# clock.net
KiCad netlist of a schematic drawn in EAGLE
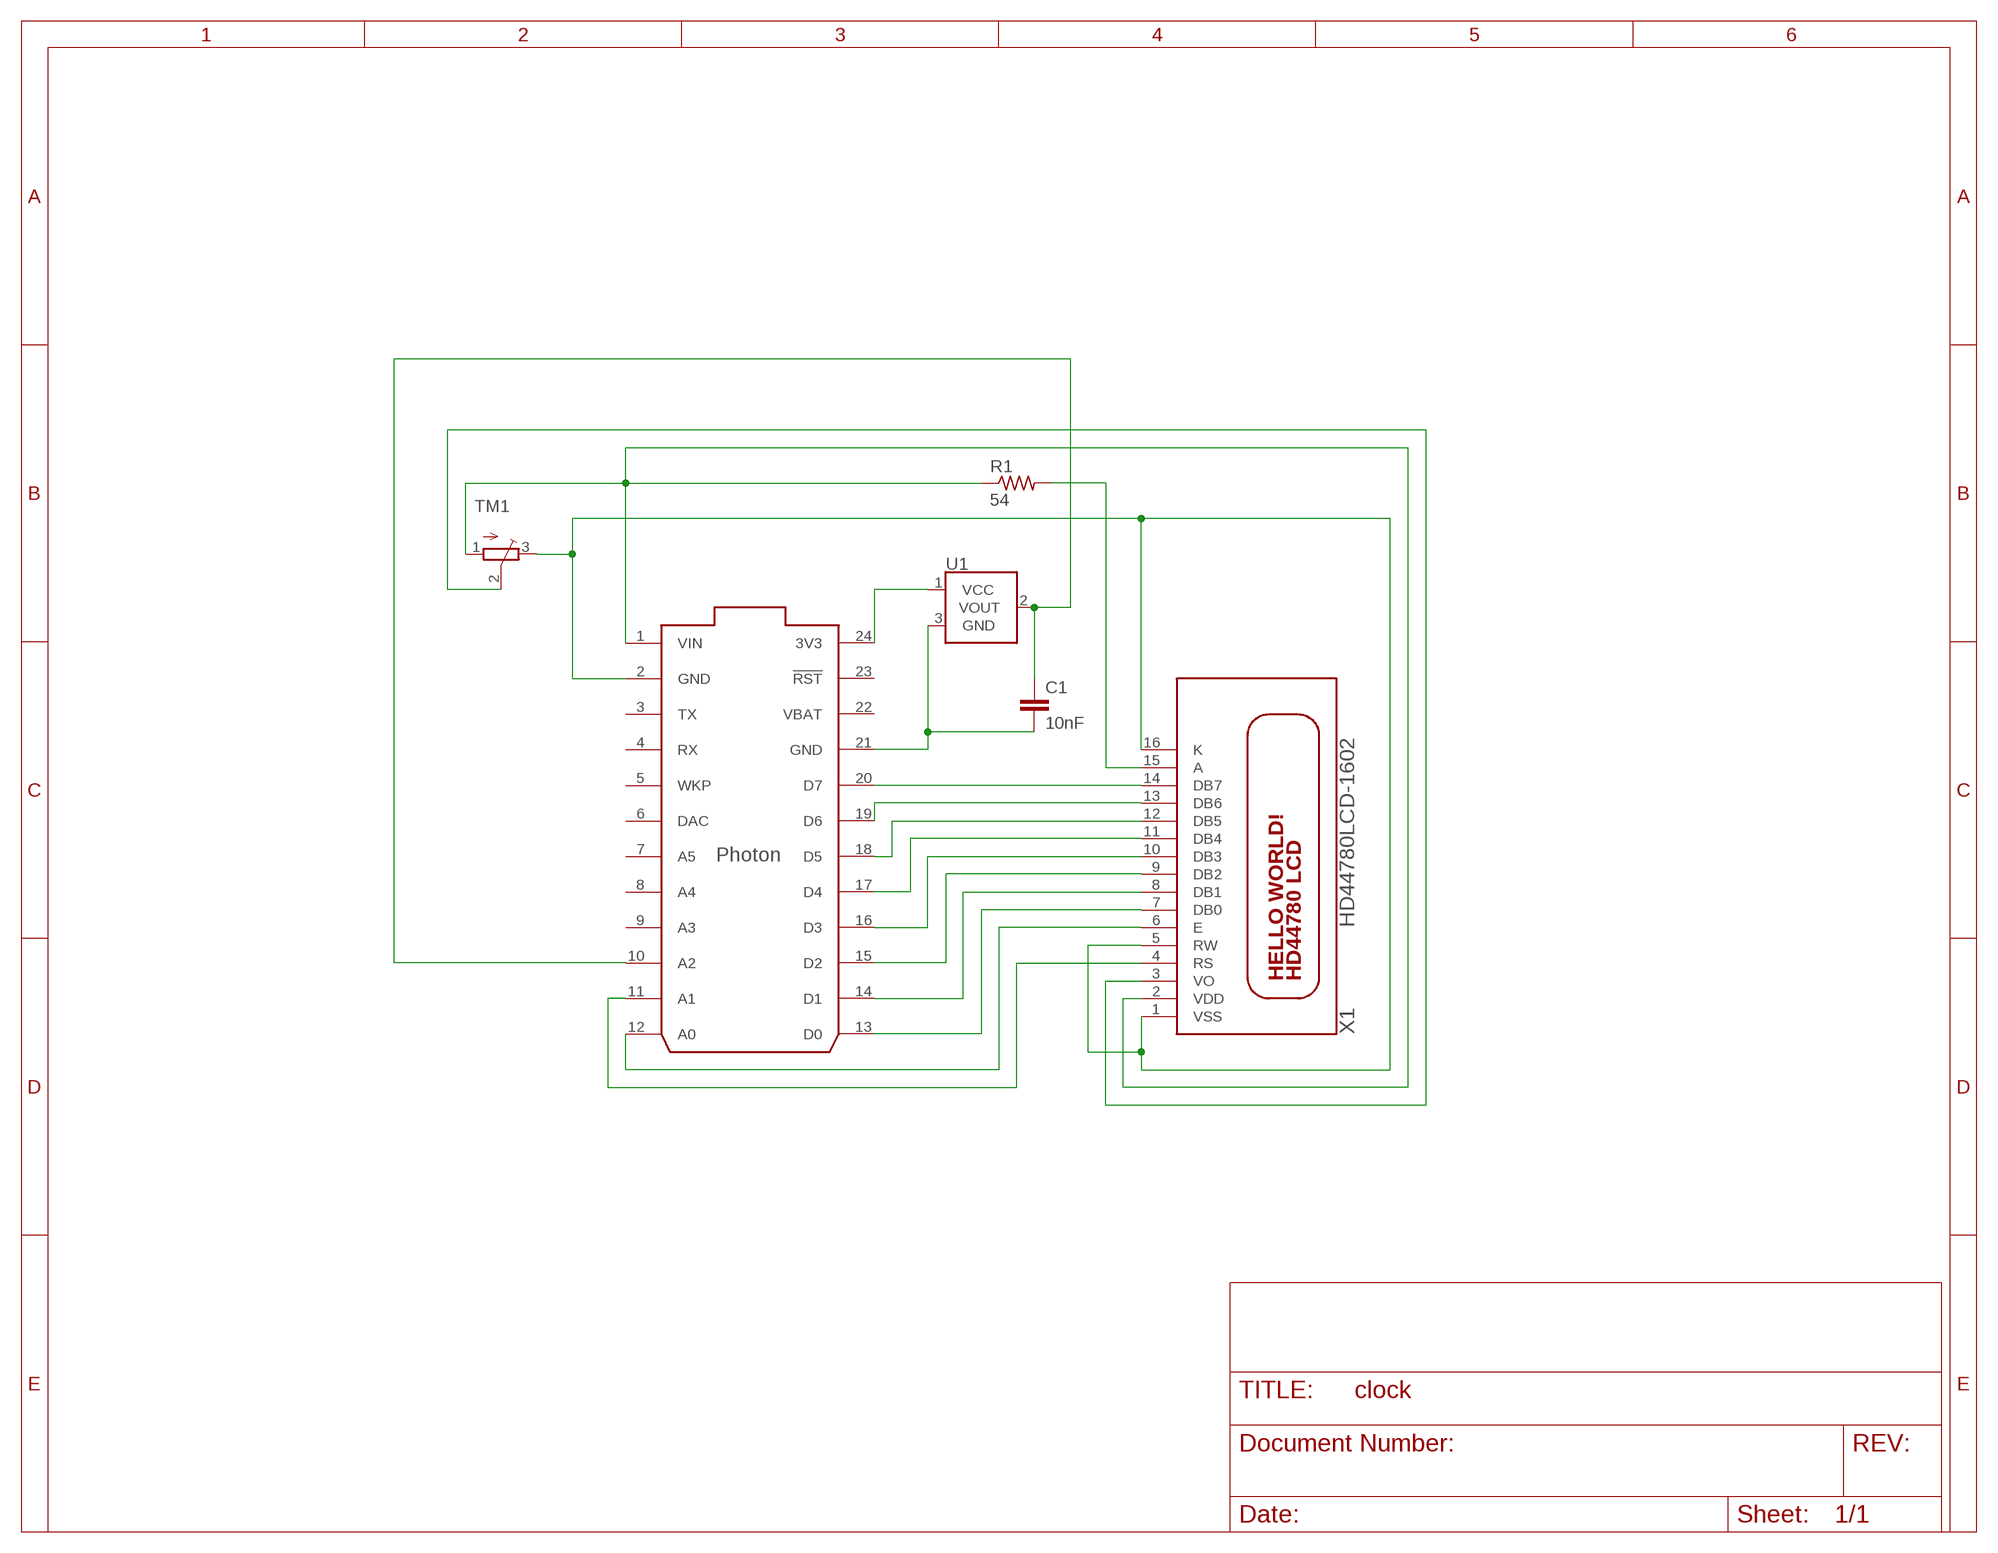
[diagram p0: schematic, sheet 1]

(export (version "E")
  (design (tool "Eeschema 10.0.6"))
  (components
    (comp (ref "C1")
      (value "10nF")
      (footprint "eagle-import:CAP-PTH-10MM")
      (libsource (lib "eagle-import") (part "10NF-PTH-10MM-10000V-1-%"))
    )
    (comp (ref "R1")
      (value "54")
      (footprint "eagle-import:0309_12")
      (libsource (lib "eagle-import") (part "R-US_0309/12"))
    )
    (comp (ref "TM1")
      (value "TRIMPOT3386")
      (footprint "eagle-import:TRIM-3386")
      (libsource (lib "eagle-import") (part "TRIMPOT3386"))
    )
    (comp (ref "U$1")
      (value "PHOTON_WITH_HEADERS")
      (footprint "eagle-import:PHOTON")
      (libsource (lib "eagle-import") (part "PHOTON_WITH_HEADERS"))
    )
    (comp (ref "U1")
      (value "TMP36GT9")
      (footprint "eagle-import:TO-92")
      (libsource (lib "eagle-import") (part "TMP36GT9"))
    )
    (comp (ref "X1")
      (value "HD44780LCD-1602")
      (footprint "eagle-import:LCD1602")
      (libsource (lib "eagle-import") (part "HD44780LCD-1602"))
    )
  )
  (nets
    (net (code "1") (name "/VBAT") (class "Default")
      (node (ref "U$1") (pin "22") (pinfunction "VBAT_22") (pintype "power_in"))
    )
    (net (code "2") (name "Net-(TM1-A)") (class "Default")
      (node (ref "R1") (pin "1") (pinfunction "1_1") (pintype "passive"))
      (node (ref "TM1") (pin "1") (pinfunction "A_1") (pintype "passive"))
      (node (ref "U$1") (pin "1") (pinfunction "VIN_1") (pintype "power_in"))
      (node (ref "X1") (pin "2") (pinfunction "VDD_2") (pintype "power_in"))
    )
    (net (code "3") (name "Net-(TM1-E)") (class "Default")
      (node (ref "TM1") (pin "3") (pinfunction "E_3") (pintype "passive"))
      (node (ref "U$1") (pin "2") (pinfunction "GND_2") (pintype "power_in"))
      (node (ref "X1") (pin "1") (pinfunction "VSS_1") (pintype "power_in"))
      (node (ref "X1") (pin "16") (pinfunction "K_16") (pintype "input"))
      (node (ref "X1") (pin "5") (pinfunction "RW_5") (pintype "input"))
    )
    (net (code "4") (name "Net-(TM1-S)") (class "Default")
      (node (ref "TM1") (pin "2") (pinfunction "S_2") (pintype "passive"))
      (node (ref "X1") (pin "3") (pinfunction "VO_3") (pintype "input"))
    )
    (net (code "5") (name "Net-(U$1-3V3)") (class "Default")
      (node (ref "U$1") (pin "24") (pinfunction "3V3_24") (pintype "power_in"))
      (node (ref "U1") (pin "1") (pinfunction "VCC_1") (pintype "bidirectional"))
    )
    (net (code "6") (name "Net-(U$1-A0)") (class "Default")
      (node (ref "U$1") (pin "12") (pinfunction "A0_12") (pintype "bidirectional"))
      (node (ref "X1") (pin "6") (pinfunction "E_6") (pintype "input"))
    )
    (net (code "7") (name "Net-(U$1-A1)") (class "Default")
      (node (ref "U$1") (pin "11") (pinfunction "A1_11") (pintype "bidirectional"))
      (node (ref "X1") (pin "4") (pinfunction "RS_4") (pintype "input"))
    )
    (net (code "8") (name "Net-(U$1-A2)") (class "Default")
      (node (ref "C1") (pin "1") (pinfunction "1_1") (pintype "passive"))
      (node (ref "U$1") (pin "10") (pinfunction "A2_10") (pintype "bidirectional"))
      (node (ref "U1") (pin "2") (pinfunction "VOUT_2") (pintype "bidirectional"))
    )
    (net (code "9") (name "Net-(U$1-D0)") (class "Default")
      (node (ref "U$1") (pin "13") (pinfunction "D0_13") (pintype "bidirectional"))
      (node (ref "X1") (pin "7") (pinfunction "DB0_7") (pintype "bidirectional"))
    )
    (net (code "10") (name "Net-(U$1-D1)") (class "Default")
      (node (ref "U$1") (pin "14") (pinfunction "D1_14") (pintype "bidirectional"))
      (node (ref "X1") (pin "8") (pinfunction "DB1_8") (pintype "bidirectional"))
    )
    (net (code "11") (name "Net-(U$1-D2)") (class "Default")
      (node (ref "U$1") (pin "15") (pinfunction "D2_15") (pintype "bidirectional"))
      (node (ref "X1") (pin "9") (pinfunction "DB2_9") (pintype "bidirectional"))
    )
    (net (code "12") (name "Net-(U$1-D3)") (class "Default")
      (node (ref "U$1") (pin "16") (pinfunction "D3_16") (pintype "bidirectional"))
      (node (ref "X1") (pin "10") (pinfunction "DB3_10") (pintype "bidirectional"))
    )
    (net (code "13") (name "Net-(U$1-D4)") (class "Default")
      (node (ref "U$1") (pin "17") (pinfunction "D4_17") (pintype "bidirectional"))
      (node (ref "X1") (pin "11") (pinfunction "DB4_11") (pintype "bidirectional"))
    )
    (net (code "14") (name "Net-(U$1-D5)") (class "Default")
      (node (ref "U$1") (pin "18") (pinfunction "D5_18") (pintype "bidirectional"))
      (node (ref "X1") (pin "12") (pinfunction "DB5_12") (pintype "bidirectional"))
    )
    (net (code "15") (name "Net-(U$1-D6)") (class "Default")
      (node (ref "U$1") (pin "19") (pinfunction "D6_19") (pintype "bidirectional"))
      (node (ref "X1") (pin "13") (pinfunction "DB6_13") (pintype "bidirectional"))
    )
    (net (code "16") (name "Net-(U$1-D7)") (class "Default")
      (node (ref "U$1") (pin "20") (pinfunction "D7_20") (pintype "bidirectional"))
      (node (ref "X1") (pin "14") (pinfunction "DB7_14") (pintype "bidirectional"))
    )
    (net (code "17") (name "Net-(U1-GND)") (class "Default")
      (node (ref "C1") (pin "2") (pinfunction "2_2") (pintype "passive"))
      (node (ref "U$1") (pin "21") (pinfunction "GND_21") (pintype "power_in"))
      (node (ref "U1") (pin "3") (pinfunction "GND_3") (pintype "bidirectional"))
    )
    (net (code "18") (name "Net-(X1-A)") (class "Default")
      (node (ref "R1") (pin "2") (pinfunction "2_2") (pintype "passive"))
      (node (ref "X1") (pin "15") (pinfunction "A_15") (pintype "input"))
    )
    (net (code "19") (name "unconnected-(U$1-A3-Pad9)") (class "Default")
      (node (ref "U$1") (pin "9") (pinfunction "A3_9") (pintype "bidirectional"))
    )
    (net (code "20") (name "unconnected-(U$1-A4-Pad8)") (class "Default")
      (node (ref "U$1") (pin "8") (pinfunction "A4_8") (pintype "bidirectional"))
    )
    (net (code "21") (name "unconnected-(U$1-A5-Pad7)") (class "Default")
      (node (ref "U$1") (pin "7") (pinfunction "A5_7") (pintype "bidirectional"))
    )
    (net (code "22") (name "unconnected-(U$1-DAC-Pad6)") (class "Default")
      (node (ref "U$1") (pin "6") (pinfunction "DAC_6") (pintype "bidirectional"))
    )
    (net (code "23") (name "unconnected-(U$1-RX-Pad4)") (class "Default")
      (node (ref "U$1") (pin "4") (pinfunction "RX_4") (pintype "bidirectional"))
    )
    (net (code "24") (name "unconnected-(U$1-TX-Pad3)") (class "Default")
      (node (ref "U$1") (pin "3") (pinfunction "TX_3") (pintype "bidirectional"))
    )
    (net (code "25") (name "unconnected-(U$1-WKP-Pad5)") (class "Default")
      (node (ref "U$1") (pin "5") (pinfunction "WKP_5") (pintype "bidirectional"))
    )
    (net (code "26") (name "unconnected-(U$1-~{RST}-Pad23)") (class "Default")
      (node (ref "U$1") (pin "23") (pinfunction "~{RST}_23") (pintype "bidirectional"))
    )
  )
)
